# Motor_Controllers.net
KiCad netlist of a schematic drawn in Altium Designer
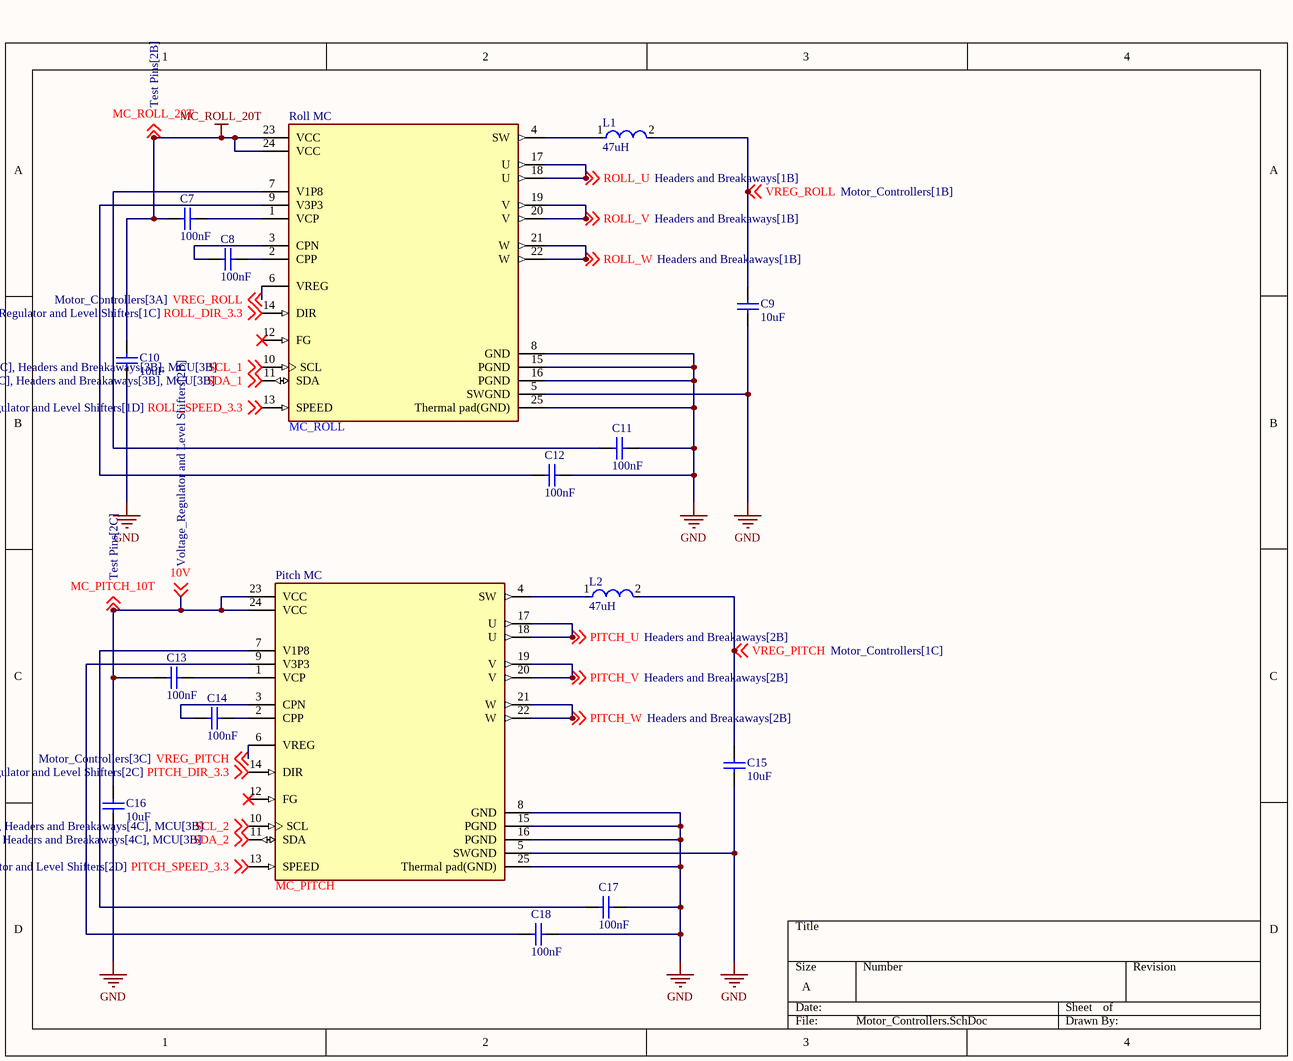
[diagram p0: Motor_Controllers.SchDoc]

(export (version "E")
  (design (tool "Eeschema 10.0.6"))
  (components
    (comp (ref "C7")
      (value "100nF")
      (footprint "0805")
      (description "CAP Ceramic, 100nF, 50V, 0805")
      (fields (field (name "MPN") "CC0805KRX7R9BB104") (field (name "JLCPCB PART #") "C49678"))
      (libsource (lib "JLCPCB Ceramic Capacitor Schematic Lib") (part "nF - 100nF (0.1uF)"))
    )
    (comp (ref "C8")
      (value "100nF")
      (footprint "0805")
      (description "CAP Ceramic, 100nF, 50V, 0805")
      (fields (field (name "MPN") "CC0805KRX7R9BB104") (field (name "JLCPCB PART #") "C49678"))
      (libsource (lib "JLCPCB Ceramic Capacitor Schematic Lib") (part "nF - 100nF (0.1uF)"))
    )
    (comp (ref "C9")
      (value "10uF")
      (footprint "0805")
      (description "CAP Ceramic, 10uF, 50V, 0805")
      (fields (field (name "MPN") "GRM21BR61H106KE43L") (field (name "JLCPCB PART #") "C440198"))
      (libsource (lib "JLCPCB Ceramic Capacitor Schematic Lib") (part "uF - 10uF"))
    )
    (comp (ref "C10")
      (value "10uF")
      (footprint "0805")
      (description "CAP Ceramic, 10uF, 50V, 0805")
      (fields (field (name "MPN") "GRM21BR61H106KE43L") (field (name "JLCPCB PART #") "C440198"))
      (libsource (lib "JLCPCB Ceramic Capacitor Schematic Lib") (part "uF - 10uF"))
    )
    (comp (ref "C11")
      (value "100nF")
      (footprint "0805")
      (description "CAP Ceramic, 100nF, 50V, 0805")
      (fields (field (name "MPN") "CC0805KRX7R9BB104") (field (name "JLCPCB PART #") "C49678"))
      (libsource (lib "JLCPCB Ceramic Capacitor Schematic Lib") (part "nF - 100nF (0.1uF)"))
    )
    (comp (ref "C12")
      (value "100nF")
      (footprint "0805")
      (description "CAP Ceramic, 100nF, 50V, 0805")
      (fields (field (name "MPN") "CC0805KRX7R9BB104") (field (name "JLCPCB PART #") "C49678"))
      (libsource (lib "JLCPCB Ceramic Capacitor Schematic Lib") (part "nF - 100nF (0.1uF)"))
    )
    (comp (ref "C13")
      (value "100nF")
      (footprint "0805")
      (description "CAP Ceramic, 100nF, 50V, 0805")
      (fields (field (name "MPN") "CC0805KRX7R9BB104") (field (name "JLCPCB PART #") "C49678"))
      (libsource (lib "JLCPCB Ceramic Capacitor Schematic Lib") (part "nF - 100nF (0.1uF)"))
    )
    (comp (ref "C14")
      (value "100nF")
      (footprint "0805")
      (description "CAP Ceramic, 100nF, 50V, 0805")
      (fields (field (name "MPN") "CC0805KRX7R9BB104") (field (name "JLCPCB PART #") "C49678"))
      (libsource (lib "JLCPCB Ceramic Capacitor Schematic Lib") (part "nF - 100nF (0.1uF)"))
    )
    (comp (ref "C15")
      (value "10uF")
      (footprint "0805")
      (description "CAP Ceramic, 10uF, 50V, 0805")
      (fields (field (name "MPN") "GRM21BR61H106KE43L") (field (name "JLCPCB PART #") "C440198"))
      (libsource (lib "JLCPCB Ceramic Capacitor Schematic Lib") (part "uF - 10uF"))
    )
    (comp (ref "C16")
      (value "10uF")
      (footprint "0805")
      (description "CAP Ceramic, 10uF, 50V, 0805")
      (fields (field (name "MPN") "GRM21BR61H106KE43L") (field (name "JLCPCB PART #") "C440198"))
      (libsource (lib "JLCPCB Ceramic Capacitor Schematic Lib") (part "uF - 10uF"))
    )
    (comp (ref "C17")
      (value "100nF")
      (footprint "0805")
      (description "CAP Ceramic, 100nF, 50V, 0805")
      (fields (field (name "MPN") "CC0805KRX7R9BB104") (field (name "JLCPCB PART #") "C49678"))
      (libsource (lib "JLCPCB Ceramic Capacitor Schematic Lib") (part "nF - 100nF (0.1uF)"))
    )
    (comp (ref "C18")
      (value "100nF")
      (footprint "0805")
      (description "CAP Ceramic, 100nF, 50V, 0805")
      (fields (field (name "MPN") "CC0805KRX7R9BB104") (field (name "JLCPCB PART #") "C49678"))
      (libsource (lib "JLCPCB Ceramic Capacitor Schematic Lib") (part "nF - 100nF (0.1uF)"))
    )
    (comp (ref "L1")
      (value "47uH")
      (footprint "FP-LQM21DH_70-IPC_A")
      (description "Multilayer Type Inductor for Power Lines, 0805 (2012), 47μH, 30%, 1.2Ω, 7mA")
      (fields (field (name "TOLERANCE") "30%") (field (name "MPN") "LQM21DN470N00L"))
      (libsource (lib "Altium Content Vault") (part "725321dda6339637d4d059423bc1c3c"))
    )
    (comp (ref "L2")
      (value "47uH")
      (footprint "FP-LQM21DH_70-IPC_A")
      (description "Multilayer Type Inductor for Power Lines, 0805 (2012), 47μH, 30%, 1.2Ω, 7mA")
      (fields (field (name "TOLERANCE") "30%") (field (name "MPN") "LQM21DN470N00L"))
      (libsource (lib "Altium Content Vault") (part "725321dda6339637d4d059423bc1c3c"))
    )
    (comp (ref "Pitch MC")
      (value "MC_PITCH")
      (footprint "FP-PWP0024B-MFG")
      (description "IC MOTOR DRIVER 8V-28V 24HTSSOP")
      (fields (field (name "MPN") "DRV10983PWPR"))
      (libsource (lib "Altium Content Vault") (part "3b3be87c503825bcfed17f481b12426"))
    )
    (comp (ref "Roll MC")
      (value "MC_ROLL")
      (footprint "FP-PWP0024B-MFG")
      (description "IC MOTOR DRIVER 8V-28V 24HTSSOP")
      (fields (field (name "MPN") "DRV10983PWPR"))
      (libsource (lib "Altium Content Vault") (part "3b3be87c503825bcfed17f481b12426"))
    )
  )
  (nets
    (net (code "1") (name "10V") (class "Default")
      (node (ref "C13") (pin "1") (pinfunction "1_1") (pintype "passive"))
      (node (ref "C16") (pin "2") (pinfunction "2_2") (pintype "passive"))
      (node (ref "Pitch MC") (pin "23") (pinfunction "VCC_23") (pintype "power_in"))
      (node (ref "Pitch MC") (pin "24") (pinfunction "VCC_24") (pintype "power_in"))
    )
    (net (code "2") (name "GND") (class "Default")
      (node (ref "C10") (pin "1") (pinfunction "1_1") (pintype "passive"))
      (node (ref "C11") (pin "2") (pinfunction "2_2") (pintype "passive"))
      (node (ref "C12") (pin "2") (pinfunction "2_2") (pintype "passive"))
      (node (ref "C15") (pin "1") (pinfunction "1_1") (pintype "passive"))
      (node (ref "C16") (pin "1") (pinfunction "1_1") (pintype "passive"))
      (node (ref "C17") (pin "2") (pinfunction "2_2") (pintype "passive"))
      (node (ref "C18") (pin "2") (pinfunction "2_2") (pintype "passive"))
      (node (ref "C9") (pin "1") (pinfunction "1_1") (pintype "passive"))
      (node (ref "Pitch MC") (pin "15") (pinfunction "PGND_15") (pintype "power_in"))
      (node (ref "Pitch MC") (pin "16") (pinfunction "PGND_16") (pintype "power_in"))
      (node (ref "Pitch MC") (pin "25") (pinfunction "Thermal_pad(GND)_25") (pintype "power_in"))
      (node (ref "Pitch MC") (pin "5") (pinfunction "SWGND_5") (pintype "power_in"))
      (node (ref "Pitch MC") (pin "8") (pinfunction "GND_8") (pintype "power_in"))
      (node (ref "Roll MC") (pin "15") (pinfunction "PGND_15") (pintype "power_in"))
      (node (ref "Roll MC") (pin "16") (pinfunction "PGND_16") (pintype "power_in"))
      (node (ref "Roll MC") (pin "25") (pinfunction "Thermal_pad(GND)_25") (pintype "power_in"))
      (node (ref "Roll MC") (pin "5") (pinfunction "SWGND_5") (pintype "power_in"))
      (node (ref "Roll MC") (pin "8") (pinfunction "GND_8") (pintype "power_in"))
    )
    (net (code "3") (name "MC_ROLL_20T") (class "Default")
      (node (ref "C10") (pin "2") (pinfunction "2_2") (pintype "passive"))
      (node (ref "C7") (pin "1") (pinfunction "1_1") (pintype "passive"))
      (node (ref "Roll MC") (pin "23") (pinfunction "VCC_23") (pintype "power_in"))
      (node (ref "Roll MC") (pin "24") (pinfunction "VCC_24") (pintype "power_in"))
    )
    (net (code "4") (name "Net-(Pitch MC-CPN)") (class "Default")
      (node (ref "C14") (pin "1") (pinfunction "1_1") (pintype "passive"))
      (node (ref "Pitch MC") (pin "3") (pinfunction "CPN_3") (pintype "power_in"))
    )
    (net (code "5") (name "Net-(Pitch MC-CPP)") (class "Default")
      (node (ref "C14") (pin "2") (pinfunction "2_2") (pintype "passive"))
      (node (ref "Pitch MC") (pin "2") (pinfunction "CPP_2") (pintype "power_in"))
    )
    (net (code "6") (name "Net-(Pitch MC-SW)") (class "Default")
      (node (ref "L2") (pin "1") (pinfunction "1_1") (pintype "passive"))
      (node (ref "Pitch MC") (pin "4") (pinfunction "SW_4") (pintype "output"))
    )
    (net (code "7") (name "Net-(Pitch MC-V1P8)") (class "Default")
      (node (ref "C17") (pin "1") (pinfunction "1_1") (pintype "passive"))
      (node (ref "Pitch MC") (pin "7") (pinfunction "V1P8_7") (pintype "power_in"))
    )
    (net (code "8") (name "Net-(Pitch MC-V3P3)") (class "Default")
      (node (ref "C18") (pin "1") (pinfunction "1_1") (pintype "passive"))
      (node (ref "Pitch MC") (pin "9") (pinfunction "V3P3_9") (pintype "power_in"))
    )
    (net (code "9") (name "Net-(Pitch MC-VCP)") (class "Default")
      (node (ref "C13") (pin "2") (pinfunction "2_2") (pintype "passive"))
      (node (ref "Pitch MC") (pin "1") (pinfunction "VCP_1") (pintype "power_in"))
    )
    (net (code "10") (name "Net-(Roll MC-CPN)") (class "Default")
      (node (ref "C8") (pin "1") (pinfunction "1_1") (pintype "passive"))
      (node (ref "Roll MC") (pin "3") (pinfunction "CPN_3") (pintype "power_in"))
    )
    (net (code "11") (name "Net-(Roll MC-CPP)") (class "Default")
      (node (ref "C8") (pin "2") (pinfunction "2_2") (pintype "passive"))
      (node (ref "Roll MC") (pin "2") (pinfunction "CPP_2") (pintype "power_in"))
    )
    (net (code "12") (name "Net-(Roll MC-SW)") (class "Default")
      (node (ref "L1") (pin "1") (pinfunction "1_1") (pintype "passive"))
      (node (ref "Roll MC") (pin "4") (pinfunction "SW_4") (pintype "output"))
    )
    (net (code "13") (name "Net-(Roll MC-V1P8)") (class "Default")
      (node (ref "C11") (pin "1") (pinfunction "1_1") (pintype "passive"))
      (node (ref "Roll MC") (pin "7") (pinfunction "V1P8_7") (pintype "power_in"))
    )
    (net (code "14") (name "Net-(Roll MC-V3P3)") (class "Default")
      (node (ref "C12") (pin "1") (pinfunction "1_1") (pintype "passive"))
      (node (ref "Roll MC") (pin "9") (pinfunction "V3P3_9") (pintype "power_in"))
    )
    (net (code "15") (name "Net-(Roll MC-VCP)") (class "Default")
      (node (ref "C7") (pin "2") (pinfunction "2_2") (pintype "passive"))
      (node (ref "Roll MC") (pin "1") (pinfunction "VCP_1") (pintype "power_in"))
    )
    (net (code "16") (name "PITCH_DIR_3.3") (class "Default")
      (node (ref "Pitch MC") (pin "14") (pinfunction "DIR_14") (pintype "input"))
    )
    (net (code "17") (name "PITCH_SPEED_3.3") (class "Default")
      (node (ref "Pitch MC") (pin "13") (pinfunction "SPEED_13") (pintype "input"))
    )
    (net (code "18") (name "PITCH_U") (class "Default")
      (node (ref "Pitch MC") (pin "17") (pinfunction "U_17") (pintype "output"))
      (node (ref "Pitch MC") (pin "18") (pinfunction "U_18") (pintype "output"))
    )
    (net (code "19") (name "PITCH_V") (class "Default")
      (node (ref "Pitch MC") (pin "19") (pinfunction "V_19") (pintype "output"))
      (node (ref "Pitch MC") (pin "20") (pinfunction "V_20") (pintype "output"))
    )
    (net (code "20") (name "PITCH_W") (class "Default")
      (node (ref "Pitch MC") (pin "21") (pinfunction "W_21") (pintype "output"))
      (node (ref "Pitch MC") (pin "22") (pinfunction "W_22") (pintype "output"))
    )
    (net (code "21") (name "ROLL_DIR_3.3") (class "Default")
      (node (ref "Roll MC") (pin "14") (pinfunction "DIR_14") (pintype "input"))
    )
    (net (code "22") (name "ROLL_SPEED_3.3") (class "Default")
      (node (ref "Roll MC") (pin "13") (pinfunction "SPEED_13") (pintype "input"))
    )
    (net (code "23") (name "ROLL_U") (class "Default")
      (node (ref "Roll MC") (pin "17") (pinfunction "U_17") (pintype "output"))
      (node (ref "Roll MC") (pin "18") (pinfunction "U_18") (pintype "output"))
    )
    (net (code "24") (name "ROLL_V") (class "Default")
      (node (ref "Roll MC") (pin "19") (pinfunction "V_19") (pintype "output"))
      (node (ref "Roll MC") (pin "20") (pinfunction "V_20") (pintype "output"))
    )
    (net (code "25") (name "ROLL_W") (class "Default")
      (node (ref "Roll MC") (pin "21") (pinfunction "W_21") (pintype "output"))
      (node (ref "Roll MC") (pin "22") (pinfunction "W_22") (pintype "output"))
    )
    (net (code "26") (name "SCL_1") (class "Default")
      (node (ref "Roll MC") (pin "10") (pinfunction "SCL_10") (pintype "input"))
    )
    (net (code "27") (name "SCL_2") (class "Default")
      (node (ref "Pitch MC") (pin "10") (pinfunction "SCL_10") (pintype "input"))
    )
    (net (code "28") (name "SDA_1") (class "Default")
      (node (ref "Roll MC") (pin "11") (pinfunction "SDA_11") (pintype "bidirectional"))
    )
    (net (code "29") (name "SDA_2") (class "Default")
      (node (ref "Pitch MC") (pin "11") (pinfunction "SDA_11") (pintype "bidirectional"))
    )
    (net (code "30") (name "VREG_PITCH") (class "Default")
      (node (ref "C15") (pin "2") (pinfunction "2_2") (pintype "passive"))
      (node (ref "L2") (pin "2") (pinfunction "2_2") (pintype "passive"))
      (node (ref "Pitch MC") (pin "6") (pinfunction "VREG_6") (pintype "power_in"))
    )
    (net (code "31") (name "VREG_ROLL") (class "Default")
      (node (ref "C9") (pin "2") (pinfunction "2_2") (pintype "passive"))
      (node (ref "L1") (pin "2") (pinfunction "2_2") (pintype "passive"))
      (node (ref "Roll MC") (pin "6") (pinfunction "VREG_6") (pintype "power_in"))
    )
    (net (code "32") (name "unconnected-(Pitch MC-FG-Pad12)") (class "Default")
      (node (ref "Pitch MC") (pin "12") (pinfunction "FG_12") (pintype "input+no_connect"))
    )
    (net (code "33") (name "unconnected-(Roll MC-FG-Pad12)") (class "Default")
      (node (ref "Roll MC") (pin "12") (pinfunction "FG_12") (pintype "input+no_connect"))
    )
  )
)
